# MainSheet.net
KiCad netlist of a schematic drawn in Altium Designer
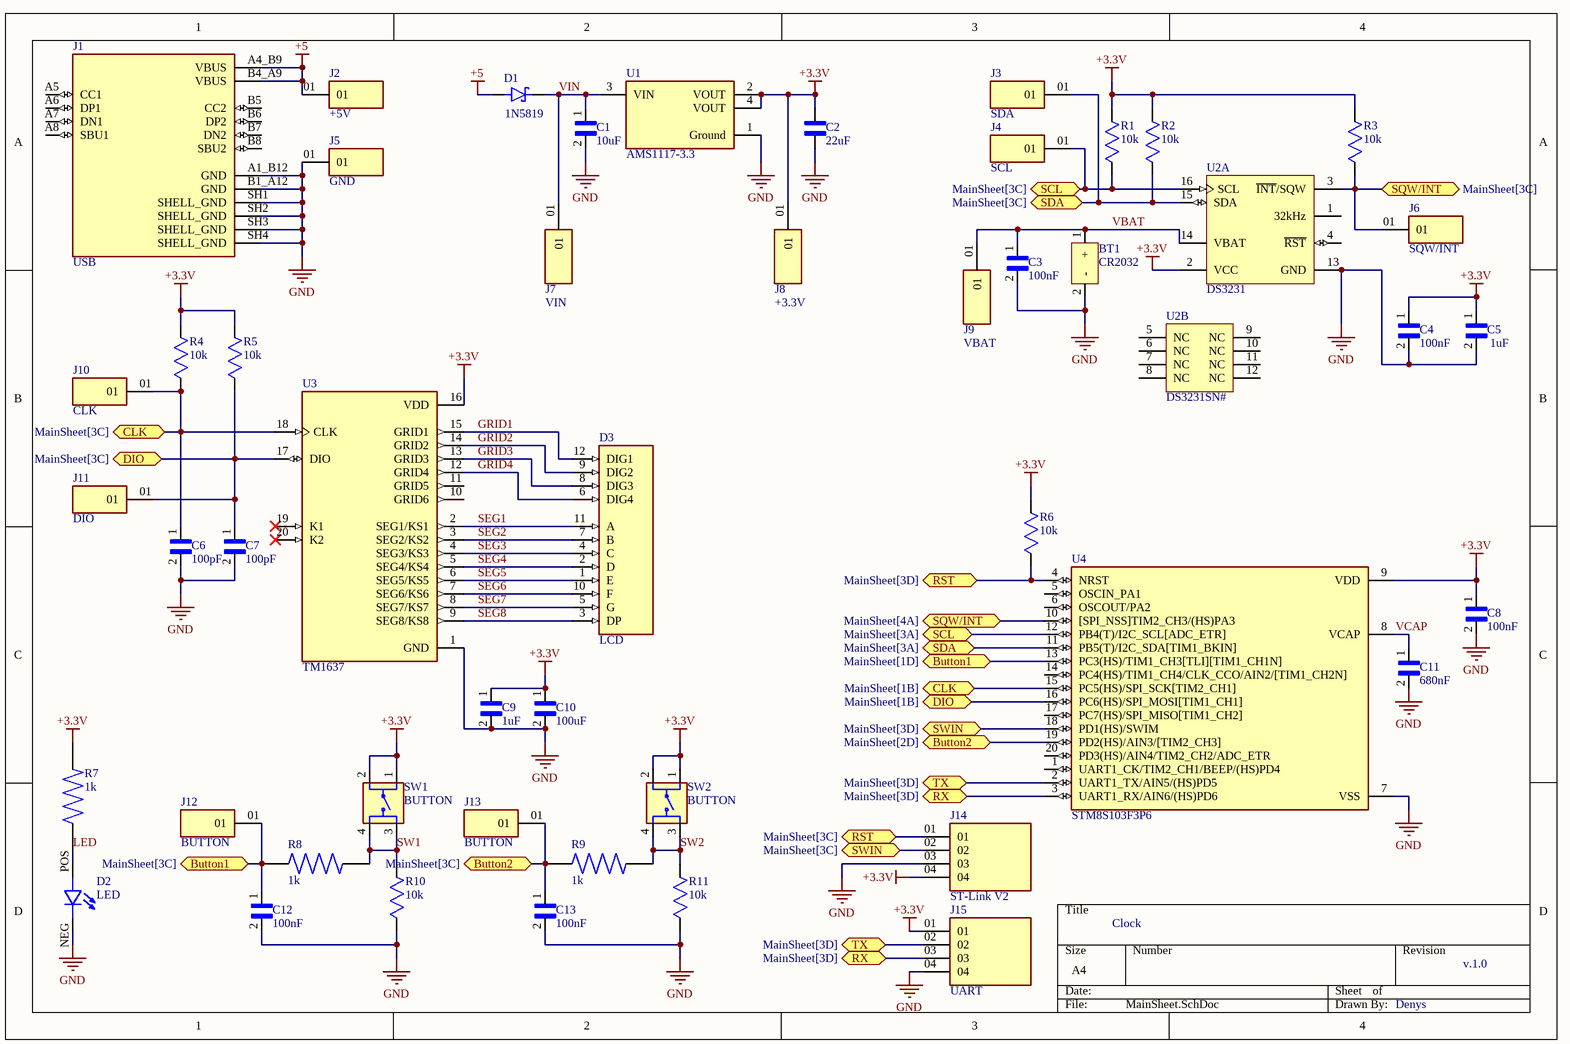
[diagram p0: MainSheet.SchDoc]

(export (version "E")
  (design (tool "Eeschema 10.0.6"))
  (components
    (comp (ref "BT1")
      (value "CR2032")
      (footprint "PCB_Battery")
      (description "Cell Holder for CR2032")
      (libsource (lib "CR2032") (part "Battery"))
    )
    (comp (ref "C1")
      (value "10uF")
      (footprint "CAPC3216X190")
      (description "Cap Ceramic 10uF 25V B 10% Pad SMD 1206 85Â°C T/R")
      (fields (field (name "MP") "GRM31CB31E106KA75L"))
      (libsource (lib "GRM31CB31E106KA75L_new") (part "GRM31CB31E106KA75L"))
    )
    (comp (ref "C2")
      (value "22uF")
      (footprint "CAPC3216X125N")
      (fields (field (name "MP") "altium_native_batch"))
      (libsource (lib "GRM31CR61E226KE15L") (part "GRM31CR61E226KE15L"))
    )
    (comp (ref "C3")
      (value "100nF")
      (footprint "CAPC3216X180N")
      (description "Ceramic capacitor SMD 1206 100 nF 50 V 10 % Samsung Electro-Mechanics CL31B104KBCNNNC 4000 pc(s)")
      (fields (field (name "MP") "CL31B104KBCNNNC") (field (name "MF") "Samsung Electro-Mechanics"))
      (libsource (lib "CL31B104KBCNNNC") (part "CL31B104KBCNNNC"))
    )
    (comp (ref "C4")
      (value "100nF")
      (footprint "CAPC3216X180N")
      (description "Ceramic capacitor SMD 1206 100 nF 50 V 10 % Samsung Electro-Mechanics CL31B104KBCNNNC 4000 pc(s)")
      (fields (field (name "MP") "CL31B104KBCNNNC") (field (name "MF") "Samsung Electro-Mechanics"))
      (libsource (lib "CL31B104KBCNNNC") (part "CL31B104KBCNNNC"))
    )
    (comp (ref "C5")
      (value "1uF")
      (footprint "CAPC3216X110N")
      (description "CAP CER 1UF 25V X7R 1206")
      (fields (field (name "MP") "C1206C105J3RACTU"))
      (libsource (lib "C_1206_1uF") (part "C1206C105J3RACTU"))
    )
    (comp (ref "C6")
      (value "100pF")
      (footprint "CAPC3216X110N")
      (description "CAP, MLCC, C0G, 100PF, 630V, 1206")
      (fields (field (name "MP") "C1206C101JBGACTU"))
      (libsource (lib "C_1206_100pF") (part "C1206C101JBGACTU"))
    )
    (comp (ref "C7")
      (value "100pF")
      (footprint "CAPC3216X110N")
      (description "CAP, MLCC, C0G, 100PF, 630V, 1206")
      (fields (field (name "MP") "C1206C101JBGACTU"))
      (libsource (lib "C_1206_100pF") (part "C1206C101JBGACTU"))
    )
    (comp (ref "C8")
      (value "100nF")
      (footprint "CAPC3216X180N")
      (description "Ceramic capacitor SMD 1206 100 nF 50 V 10 % Samsung Electro-Mechanics CL31B104KBCNNNC 4000 pc(s)")
      (fields (field (name "MP") "CL31B104KBCNNNC") (field (name "MF") "Samsung Electro-Mechanics"))
      (libsource (lib "CL31B104KBCNNNC") (part "CL31B104KBCNNNC"))
    )
    (comp (ref "C9")
      (value "1uF")
      (footprint "CAPC3216X110N")
      (description "CAP CER 1UF 25V X7R 1206")
      (fields (field (name "MP") "C1206C105J3RACTU"))
      (libsource (lib "C_1206_1uF") (part "C1206C105J3RACTU"))
    )
    (comp (ref "C10")
      (value "100uF")
      (footprint "CAP3216X125N")
      (description "100礔 卤10% 6.3V Ceramic Capacitor X5R 1206 _3216 Metric_")
      (fields (field (name "MF") "Murata Electronics") (field (name "MP") "GRM31CR60J107KE39L"))
      (libsource (lib "C_1206_100uF") (part "GRM31CR60J107KE39L"))
    )
    (comp (ref "C11")
      (value "680nF")
      (footprint "CAPC3216X110N")
      (description ".68UF 50V 10% 1206")
      (fields (field (name "MP") "C1206C684K5RACTU"))
      (libsource (lib "C_1206_680nF") (part "C1206C684K5RACTU"))
    )
    (comp (ref "C12")
      (value "100nF")
      (footprint "CAPC3216X180N")
      (description "Ceramic capacitor SMD 1206 100 nF 50 V 10 % Samsung Electro-Mechanics CL31B104KBCNNNC 4000 pc(s)")
      (fields (field (name "MP") "CL31B104KBCNNNC") (field (name "MF") "Samsung Electro-Mechanics"))
      (libsource (lib "CL31B104KBCNNNC") (part "CL31B104KBCNNNC"))
    )
    (comp (ref "C13")
      (value "100nF")
      (footprint "CAPC3216X180N")
      (description "Ceramic capacitor SMD 1206 100 nF 50 V 10 % Samsung Electro-Mechanics CL31B104KBCNNNC 4000 pc(s)")
      (fields (field (name "MP") "CL31B104KBCNNNC") (field (name "MF") "Samsung Electro-Mechanics"))
      (libsource (lib "CL31B104KBCNNNC") (part "CL31B104KBCNNNC"))
    )
    (comp (ref "D1")
      (value "1N5819")
      (footprint "SOD3715X145N")
      (description "Diode Schottky 40 V 1A Surface Mount SOD-123")
      (fields (field (name "MF") "Diodes Inc.") (field (name "MP") "1N5819HW-7"))
      (libsource (lib "1N5819HW-7") (part "1N5819HW-7"))
    )
    (comp (ref "D2")
      (value "LED")
      (footprint "LED_1206:LEDC3216X120N")
      (description "2.6 V Red LED SMD")
      (fields (field (name "MP") "LHN974 RED LED 1206") (field (name "MF") "Osram"))
      (libsource (lib "LED_1206") (part "LHN974_RED_LED_1206"))
    )
    (comp (ref "D3")
      (value "LCD")
      (footprint "LED_LDQ-M3604RI")
      (description "Display, Seven Segment, 9.2MM, Red")
      (fields (field (name "MF") "Lumex") (field (name "MP") "LDQ-M3604RI"))
      (libsource (lib "LED_clock") (part "LDQ-M3604RI"))
    )
    (comp (ref "J1")
      (value "USB")
      (footprint "GCT_USB4105-GF-A")
      (fields (field (name "MF") "{'manufacturer': u'GCT'}") (field (name "MP") "USB4105-GF-A"))
      (libsource (lib "USB4105-GF-A_new") (part "USB4105-GF-A"))
    )
    (comp (ref "J2")
      (value "+5V")
      (footprint "SAMTEC_MTMM-101-X-X-S-X")
      (description "Connector Header Through Hole 1 position")
      (fields (field (name "MF") "Samtec") (field (name "MP") "MTMM-101-05-G-S-225"))
      (libsource (lib "") (part "MTMM-101-X-X-S-X_2"))
    )
    (comp (ref "J3")
      (value "SDA")
      (footprint "SAMTEC_MTMM-101-X-X-S-X")
      (description "Connector Header Through Hole 1 position")
      (fields (field (name "MF") "Samtec") (field (name "MP") "MTMM-101-05-G-S-225"))
      (libsource (lib "") (part "MTMM-101-X-X-S-X_1"))
    )
    (comp (ref "J4")
      (value "SCL")
      (footprint "SAMTEC_MTMM-101-X-X-S-X")
      (description "Connector Header Through Hole 1 position")
      (fields (field (name "MF") "Samtec") (field (name "MP") "MTMM-101-05-G-S-225"))
      (libsource (lib "") (part "MTMM-101-X-X-S-X_1"))
    )
    (comp (ref "J5")
      (value "GND")
      (footprint "SAMTEC_MTMM-101-X-X-S-X")
      (description "Connector Header Through Hole 1 position")
      (fields (field (name "MF") "Samtec") (field (name "MP") "MTMM-101-05-G-S-225"))
      (libsource (lib "") (part "MTMM-101-X-X-S-X_2"))
    )
    (comp (ref "J6")
      (value "SQW/INT")
      (footprint "SAMTEC_MTMM-101-X-X-S-X")
      (description "Connector Header Through Hole 1 position")
      (fields (field (name "MF") "Samtec") (field (name "MP") "MTMM-101-05-G-S-225"))
      (libsource (lib "") (part "MTMM-101-X-X-S-X_2"))
    )
    (comp (ref "J7")
      (value "VIN")
      (footprint "SAMTEC_MTMM-101-X-X-S-X")
      (description "Connector Header Through Hole 1 position")
      (fields (field (name "MF") "Samtec") (field (name "MP") "MTMM-101-05-G-S-225"))
      (libsource (lib "MTMM-101-X-X-S-X") (part "MTMM-101-X-X-S-X"))
    )
    (comp (ref "J8")
      (value "+3.3V")
      (footprint "SAMTEC_MTMM-101-X-X-S-X")
      (description "Connector Header Through Hole 1 position")
      (fields (field (name "MF") "Samtec") (field (name "MP") "MTMM-101-05-G-S-225"))
      (libsource (lib "MTMM-101-X-X-S-X") (part "MTMM-101-X-X-S-X"))
    )
    (comp (ref "J9")
      (value "VBAT")
      (footprint "SAMTEC_MTMM-101-X-X-S-X")
      (description "Connector Header Through Hole 1 position")
      (fields (field (name "MF") "Samtec") (field (name "MP") "MTMM-101-05-G-S-225"))
      (libsource (lib "MTMM-101-X-X-S-X") (part "MTMM-101-X-X-S-X"))
    )
    (comp (ref "J10")
      (value "CLK")
      (footprint "SAMTEC_MTMM-101-X-X-S-X")
      (description "Connector Header Through Hole 1 position")
      (fields (field (name "MF") "Samtec") (field (name "MP") "MTMM-101-05-G-S-225"))
      (libsource (lib "") (part "MTMM-101-X-X-S-X_1"))
    )
    (comp (ref "J11")
      (value "DIO")
      (footprint "SAMTEC_MTMM-101-X-X-S-X")
      (description "Connector Header Through Hole 1 position")
      (fields (field (name "MF") "Samtec") (field (name "MP") "MTMM-101-05-G-S-225"))
      (libsource (lib "") (part "MTMM-101-X-X-S-X_1"))
    )
    (comp (ref "J12")
      (value "BUTTON")
      (footprint "SAMTEC_MTMM-101-X-X-S-X")
      (description "Connector Header Through Hole 1 position")
      (fields (field (name "MF") "Samtec") (field (name "MP") "MTMM-101-05-G-S-225"))
      (libsource (lib "") (part "MTMM-101-X-X-S-X_1"))
    )
    (comp (ref "J13")
      (value "BUTTON")
      (footprint "SAMTEC_MTMM-101-X-X-S-X")
      (description "Connector Header Through Hole 1 position")
      (fields (field (name "MF") "Samtec") (field (name "MP") "MTMM-101-05-G-S-225"))
      (libsource (lib "") (part "MTMM-101-X-X-S-X_1"))
    )
    (comp (ref "J14")
      (value "ST-Link V2")
      (footprint "SAMTEC_TSW-104-07-S-S")
      (fields (field (name "MF") "Samtec Inc.") (field (name "MP") "TSW-104-07-S-S"))
      (libsource (lib "TSW-104-07-S-S") (part "TSW-104-07-S-S"))
    )
    (comp (ref "J15")
      (value "UART")
      (footprint "SAMTEC_TSW-104-07-S-S")
      (fields (field (name "MF") "Samtec Inc.") (field (name "MP") "TSW-104-07-S-S"))
      (libsource (lib "TSW-104-07-S-S") (part "TSW-104-07-S-S"))
    )
    (comp (ref "R1")
      (value "10k")
      (footprint "RESC3216X71N")
      (fields (field (name "MF") "Yageo Corporation") (field (name "MP") "RC1206FR0710KL"))
      (libsource (lib "RC1206FR-0710KL") (part "RC1206FR-0710KL"))
    )
    (comp (ref "R2")
      (value "10k")
      (footprint "RESC3216X71N")
      (fields (field (name "MF") "Yageo Corporation") (field (name "MP") "RC1206FR0710KL"))
      (libsource (lib "RC1206FR-0710KL") (part "RC1206FR-0710KL"))
    )
    (comp (ref "R3")
      (value "10k")
      (footprint "RESC3216X71N")
      (fields (field (name "MF") "Yageo Corporation") (field (name "MP") "RC1206FR0710KL"))
      (libsource (lib "RC1206FR-0710KL") (part "RC1206FR-0710KL"))
    )
    (comp (ref "R4")
      (value "10k")
      (footprint "RESC3216X71N")
      (fields (field (name "MF") "Yageo Corporation") (field (name "MP") "RC1206FR0710KL"))
      (libsource (lib "RC1206FR-0710KL") (part "RC1206FR-0710KL"))
    )
    (comp (ref "R5")
      (value "10k")
      (footprint "RESC3216X71N")
      (fields (field (name "MF") "Yageo Corporation") (field (name "MP") "RC1206FR0710KL"))
      (libsource (lib "RC1206FR-0710KL") (part "RC1206FR-0710KL"))
    )
    (comp (ref "R6")
      (value "10k")
      (footprint "RESC3216X71N")
      (fields (field (name "MF") "Yageo Corporation") (field (name "MP") "RC1206FR0710KL"))
      (libsource (lib "RC1206FR-0710KL") (part "RC1206FR-0710KL"))
    )
    (comp (ref "R7")
      (value "1k")
      (footprint "RESC3116X65N")
      (description "Surge Chip Resistor Automotive Grade Thick Film 1206 1kOhm 1% Paper T/R")
      (fields (field (name "MF") "Yageo Corporation") (field (name "MP") "SR1206FR071KL"))
      (libsource (lib "SR1206FR-071KL") (part "SR1206FR-071KL"))
    )
    (comp (ref "R8")
      (value "1k")
      (footprint "RESC3116X65N")
      (description "Surge Chip Resistor Automotive Grade Thick Film 1206 1kOhm 1% Paper T/R")
      (fields (field (name "MF") "Yageo Corporation") (field (name "MP") "SR1206FR071KL"))
      (libsource (lib "SR1206FR-071KL") (part "SR1206FR-071KL"))
    )
    (comp (ref "R9")
      (value "1k")
      (footprint "RESC3116X65N")
      (description "Surge Chip Resistor Automotive Grade Thick Film 1206 1kOhm 1% Paper T/R")
      (fields (field (name "MF") "Yageo Corporation") (field (name "MP") "SR1206FR071KL"))
      (libsource (lib "SR1206FR-071KL") (part "SR1206FR-071KL"))
    )
    (comp (ref "R10")
      (value "10k")
      (footprint "RESC3216X71N")
      (fields (field (name "MF") "Yageo Corporation") (field (name "MP") "RC1206FR0710KL"))
      (libsource (lib "RC1206FR-0710KL") (part "RC1206FR-0710KL"))
    )
    (comp (ref "R11")
      (value "10k")
      (footprint "RESC3216X71N")
      (fields (field (name "MF") "Yageo Corporation") (field (name "MP") "RC1206FR0710KL"))
      (libsource (lib "RC1206FR-0710KL") (part "RC1206FR-0710KL"))
    )
    (comp (ref "SW1")
      (value "BUTTON")
      (footprint "TE_4-1437565-9")
      (description "Alcoswitch, Switch, Tactile, 50 mA, SPST, Pushbutton, Off[On], FSM6JSMA ¦ TE Connectivity FSM6JSMA")
      (fields (field (name "MF") "TE Connectivity") (field (name "MP") "FSM6JSMA"))
      (libsource (lib "4-1437565-9") (part "4-1437565-9"))
    )
    (comp (ref "SW2")
      (value "BUTTON")
      (footprint "TE_4-1437565-9")
      (description "Alcoswitch, Switch, Tactile, 50 mA, SPST, Pushbutton, Off[On], FSM6JSMA ¦ TE Connectivity FSM6JSMA")
      (fields (field (name "MF") "TE Connectivity") (field (name "MP") "FSM6JSMA"))
      (libsource (lib "4-1437565-9") (part "4-1437565-9"))
    )
    (comp (ref "U1")
      (value "AMS1117-3.3")
      (footprint "FP-AMS1117-IPC_A")
      (description "LDO Voltage Regulators 1A, 3.3V")
      (fields
        (field (name "OCTOPART") "https://octopart.com/ams1117-3.3-advanced+monolithic+systems-25899300")
        (field (name "MANUFACTURER") "Advanced Monolithic Systems")
      )
      (libsource (lib "Altium Content Vault") (part "8bdbb5f8e77002000e30dd2845d0354"))
    )
    (comp (ref "U2")
      (value "DS3231")
      (footprint "W16#H2_N")
      (libsource (lib "Altium Content Vault") (part "MAX-RTC-16-DS3231S-W16#H2"))
    )
    (comp (ref "U3")
      (value "TM1637")
      (footprint "SOIC127P1035X255-20N")
      (description "LED Drive Control Special Circuit")
      (fields (field (name "MF") "Titan Micro Electronics") (field (name "MP") "TM1637_SOP20"))
      (libsource (lib "TM1637_SOP20") (part "TM1637_SOP20"))
    )
    (comp (ref "U4")
      (value "STM8S103F3P6")
      (footprint "SOP65P640X120-20N")
      (description "STM8 series Microcontroller IC 8-Bit 16MHz 8KB (8K x 8) FLASH 20-TSSOP")
      (fields (field (name "MF") "STMicroelectronics"))
      (libsource (lib "STM8S103F3P6_new") (part "STM8S103F3P6"))
    )
  )
  (nets
    (net (code "1") (name "+3.3V") (class "Default")
      (node (ref "C10") (pin "1") (pinfunction "1_1") (pintype "passive"))
      (node (ref "C2") (pin "2") (pinfunction "2_2") (pintype "passive"))
      (node (ref "C4") (pin "1") (pinfunction "1_1") (pintype "passive"))
      (node (ref "C5") (pin "1") (pinfunction "1_1") (pintype "passive"))
      (node (ref "C8") (pin "1") (pinfunction "1_1") (pintype "passive"))
      (node (ref "C9") (pin "1") (pinfunction "1_1") (pintype "passive"))
      (node (ref "J14") (pin "04") (pinfunction "04_04") (pintype "passive"))
      (node (ref "J15") (pin "01") (pinfunction "01_01") (pintype "passive"))
      (node (ref "J8") (pin "01") (pinfunction "01_01") (pintype "passive"))
      (node (ref "R1") (pin "1") (pinfunction "R1_1") (pintype "passive"))
      (node (ref "R2") (pin "1") (pinfunction "R1_1") (pintype "passive"))
      (node (ref "R3") (pin "1") (pinfunction "R1_1") (pintype "passive"))
      (node (ref "R4") (pin "1") (pinfunction "R1_1") (pintype "passive"))
      (node (ref "R5") (pin "1") (pinfunction "R1_1") (pintype "passive"))
      (node (ref "R6") (pin "1") (pinfunction "R1_1") (pintype "passive"))
      (node (ref "R7") (pin "2") (pinfunction "2_2") (pintype "passive"))
      (node (ref "SW1") (pin "1") (pinfunction "1_1") (pintype "passive"))
      (node (ref "SW1") (pin "2") (pinfunction "2_2") (pintype "passive"))
      (node (ref "SW2") (pin "1") (pinfunction "1_1") (pintype "passive"))
      (node (ref "SW2") (pin "2") (pinfunction "2_2") (pintype "passive"))
      (node (ref "U1") (pin "2") (pinfunction "VOUT_2") (pintype "passive"))
      (node (ref "U1") (pin "4") (pinfunction "VOUT_4") (pintype "passive"))
      (node (ref "U2") (pin "2") (pinfunction "VCC_2") (pintype "power_in"))
      (node (ref "U3") (pin "16") (pinfunction "VDD_16") (pintype "power_in"))
      (node (ref "U4") (pin "9") (pinfunction "VDD_9") (pintype "power_in"))
    )
    (net (code "2") (name "+5") (class "Default")
      (node (ref "D1") (pin "A") (pinfunction "A_A") (pintype "passive"))
      (node (ref "J1") (pin "A4_B9") (pinfunction "VBUS_A4_B9") (pintype "power_in"))
      (node (ref "J1") (pin "B4_A9") (pinfunction "VBUS_B4_A9") (pintype "power_in"))
      (node (ref "J2") (pin "01") (pinfunction "01_01") (pintype "passive"))
    )
    (net (code "3") (name "/Button1") (class "Default")
      (node (ref "C12") (pin "1") (pinfunction "1_1") (pintype "passive"))
      (node (ref "J12") (pin "01") (pinfunction "01_01") (pintype "passive"))
      (node (ref "R8") (pin "2") (pinfunction "2_2") (pintype "passive"))
      (node (ref "U4") (pin "13") (pinfunction "PC3(HS)/TIM1_CH3[TLI][TIM1_CH1N]_13") (pintype "bidirectional"))
    )
    (net (code "4") (name "/Button2") (class "Default")
      (node (ref "C13") (pin "1") (pinfunction "1_1") (pintype "passive"))
      (node (ref "J13") (pin "01") (pinfunction "01_01") (pintype "passive"))
      (node (ref "R9") (pin "2") (pinfunction "2_2") (pintype "passive"))
      (node (ref "U4") (pin "19") (pinfunction "PD2(HS)/AIN3/[TIM2_CH3]_19") (pintype "bidirectional"))
    )
    (net (code "5") (name "/CLK") (class "Default")
      (node (ref "C6") (pin "1") (pinfunction "1_1") (pintype "passive"))
      (node (ref "J10") (pin "01") (pinfunction "01_01") (pintype "passive"))
      (node (ref "R4") (pin "2") (pinfunction "R2_2") (pintype "passive"))
      (node (ref "U3") (pin "18") (pinfunction "CLK_18") (pintype "input"))
      (node (ref "U4") (pin "15") (pinfunction "PC5(HS)/SPI_SCK[TIM2_CH1]_15") (pintype "bidirectional"))
    )
    (net (code "6") (name "/DIO") (class "Default")
      (node (ref "C7") (pin "1") (pinfunction "1_1") (pintype "passive"))
      (node (ref "J11") (pin "01") (pinfunction "01_01") (pintype "passive"))
      (node (ref "R5") (pin "2") (pinfunction "R2_2") (pintype "passive"))
      (node (ref "U3") (pin "17") (pinfunction "DIO_17") (pintype "bidirectional"))
      (node (ref "U4") (pin "16") (pinfunction "PC6(HS)/SPI_MOSI[TIM1_CH1]_16") (pintype "bidirectional"))
    )
    (net (code "7") (name "/GRID1") (class "Default")
      (node (ref "D3") (pin "12") (pinfunction "DIG1_12") (pintype "input"))
      (node (ref "U3") (pin "15") (pinfunction "GRID1_15") (pintype "output"))
    )
    (net (code "8") (name "/GRID2") (class "Default")
      (node (ref "D3") (pin "9") (pinfunction "DIG2_9") (pintype "input"))
      (node (ref "U3") (pin "14") (pinfunction "GRID2_14") (pintype "output"))
    )
    (net (code "9") (name "/GRID3") (class "Default")
      (node (ref "D3") (pin "8") (pinfunction "DIG3_8") (pintype "input"))
      (node (ref "U3") (pin "13") (pinfunction "GRID3_13") (pintype "output"))
    )
    (net (code "10") (name "/GRID4") (class "Default")
      (node (ref "D3") (pin "6") (pinfunction "DIG4_6") (pintype "input"))
      (node (ref "U3") (pin "12") (pinfunction "GRID4_12") (pintype "output"))
    )
    (net (code "11") (name "/LED") (class "Default")
      (node (ref "D2") (pin "POS") (pinfunction "POS_POS") (pintype "passive"))
      (node (ref "R7") (pin "1") (pinfunction "1_1") (pintype "passive"))
    )
    (net (code "12") (name "/RST") (class "Default")
      (node (ref "J14") (pin "01") (pinfunction "01_01") (pintype "passive"))
      (node (ref "R6") (pin "2") (pinfunction "R2_2") (pintype "passive"))
      (node (ref "U4") (pin "4") (pinfunction "NRST_4") (pintype "bidirectional"))
    )
    (net (code "13") (name "/RX") (class "Default")
      (node (ref "J15") (pin "03") (pinfunction "03_03") (pintype "passive"))
      (node (ref "U4") (pin "3") (pinfunction "UART1_RX/AIN6/(HS)PD6_3") (pintype "bidirectional"))
    )
    (net (code "14") (name "/SCL") (class "Default")
      (node (ref "J4") (pin "01") (pinfunction "01_01") (pintype "passive"))
      (node (ref "R1") (pin "2") (pinfunction "R2_2") (pintype "passive"))
      (node (ref "U2") (pin "16") (pinfunction "SCL_16") (pintype "input"))
      (node (ref "U4") (pin "12") (pinfunction "PB4(T)/I2C_SCL[ADC_ETR]_12") (pintype "bidirectional"))
    )
    (net (code "15") (name "/SDA") (class "Default")
      (node (ref "J3") (pin "01") (pinfunction "01_01") (pintype "passive"))
      (node (ref "R2") (pin "2") (pinfunction "R2_2") (pintype "passive"))
      (node (ref "U2") (pin "15") (pinfunction "SDA_15") (pintype "bidirectional"))
      (node (ref "U4") (pin "11") (pinfunction "PB5(T)/I2C_SDA[TIM1_BKIN]_11") (pintype "bidirectional"))
    )
    (net (code "16") (name "/SEG1") (class "Default")
      (node (ref "D3") (pin "11") (pinfunction "A_11") (pintype "input"))
      (node (ref "U3") (pin "2") (pinfunction "SEG1/KS1_2") (pintype "output"))
    )
    (net (code "17") (name "/SEG2") (class "Default")
      (node (ref "D3") (pin "7") (pinfunction "B_7") (pintype "input"))
      (node (ref "U3") (pin "3") (pinfunction "SEG2/KS2_3") (pintype "output"))
    )
    (net (code "18") (name "/SEG3") (class "Default")
      (node (ref "D3") (pin "4") (pinfunction "C_4") (pintype "input"))
      (node (ref "U3") (pin "4") (pinfunction "SEG3/KS3_4") (pintype "output"))
    )
    (net (code "19") (name "/SEG4") (class "Default")
      (node (ref "D3") (pin "2") (pinfunction "D_2") (pintype "input"))
      (node (ref "U3") (pin "5") (pinfunction "SEG4/KS4_5") (pintype "output"))
    )
    (net (code "20") (name "/SEG5") (class "Default")
      (node (ref "D3") (pin "1") (pinfunction "E_1") (pintype "input"))
      (node (ref "U3") (pin "6") (pinfunction "SEG5/KS5_6") (pintype "output"))
    )
    (net (code "21") (name "/SEG6") (class "Default")
      (node (ref "D3") (pin "10") (pinfunction "F_10") (pintype "input"))
      (node (ref "U3") (pin "7") (pinfunction "SEG6/KS6_7") (pintype "output"))
    )
    (net (code "22") (name "/SEG7") (class "Default")
      (node (ref "D3") (pin "5") (pinfunction "G_5") (pintype "input"))
      (node (ref "U3") (pin "8") (pinfunction "SEG7/KS7_8") (pintype "output"))
    )
    (net (code "23") (name "/SEG8") (class "Default")
      (node (ref "D3") (pin "3") (pinfunction "DP_3") (pintype "input"))
      (node (ref "U3") (pin "9") (pinfunction "SEG8/KS8_9") (pintype "output"))
    )
    (net (code "24") (name "/SQW{slash}INT") (class "Default")
      (node (ref "J6") (pin "01") (pinfunction "01_01") (pintype "passive"))
      (node (ref "R3") (pin "2") (pinfunction "R2_2") (pintype "passive"))
      (node (ref "U2") (pin "3") (pinfunction "~{INT}/SQW_3") (pintype "open_collector"))
      (node (ref "U4") (pin "10") (pinfunction "[SPI_NSS]TIM2_CH3/(HS)PA3_10") (pintype "bidirectional"))
    )
    (net (code "25") (name "/SW1") (class "Default")
      (node (ref "R10") (pin "1") (pinfunction "R1_1") (pintype "passive"))
      (node (ref "R8") (pin "1") (pinfunction "1_1") (pintype "passive"))
      (node (ref "SW1") (pin "3") (pinfunction "3_3") (pintype "passive"))
      (node (ref "SW1") (pin "4") (pinfunction "4_4") (pintype "passive"))
    )
    (net (code "26") (name "/SW2") (class "Default")
      (node (ref "R11") (pin "1") (pinfunction "R1_1") (pintype "passive"))
      (node (ref "R9") (pin "1") (pinfunction "1_1") (pintype "passive"))
      (node (ref "SW2") (pin "3") (pinfunction "3_3") (pintype "passive"))
      (node (ref "SW2") (pin "4") (pinfunction "4_4") (pintype "passive"))
    )
    (net (code "27") (name "/SWIN") (class "Default")
      (node (ref "J14") (pin "02") (pinfunction "02_02") (pintype "passive"))
      (node (ref "U4") (pin "18") (pinfunction "PD1(HS)/SWIM_18") (pintype "bidirectional"))
    )
    (net (code "28") (name "/TX") (class "Default")
      (node (ref "J15") (pin "02") (pinfunction "02_02") (pintype "passive"))
      (node (ref "U4") (pin "2") (pinfunction "UART1_TX/AIN5/(HS)PD5_2") (pintype "bidirectional"))
    )
    (net (code "29") (name "/VBAT") (class "Default")
      (node (ref "BT1") (pin "1") (pinfunction "+_1") (pintype "power_in"))
      (node (ref "C3") (pin "1") (pinfunction "1_1") (pintype "passive"))
      (node (ref "J9") (pin "01") (pinfunction "01_01") (pintype "passive"))
      (node (ref "U2") (pin "14") (pinfunction "VBAT_14") (pintype "power_in"))
    )
    (net (code "30") (name "/VCAP") (class "Default")
      (node (ref "C11") (pin "1") (pinfunction "1_1") (pintype "passive"))
      (node (ref "U4") (pin "8") (pinfunction "VCAP_8") (pintype "passive"))
    )
    (net (code "31") (name "/VIN") (class "Default")
      (node (ref "C1") (pin "1") (pinfunction "1_1") (pintype "passive"))
      (node (ref "D1") (pin "C") (pinfunction "K_C") (pintype "passive"))
      (node (ref "J7") (pin "01") (pinfunction "01_01") (pintype "passive"))
      (node (ref "U1") (pin "3") (pinfunction "VIN_3") (pintype "power_in"))
    )
    (net (code "32") (name "GND") (class "Default")
      (node (ref "BT1") (pin "2") (pinfunction "-_2") (pintype "power_in"))
      (node (ref "C1") (pin "2") (pinfunction "2_2") (pintype "passive"))
      (node (ref "C10") (pin "2") (pinfunction "2_2") (pintype "passive"))
      (node (ref "C11") (pin "2") (pinfunction "2_2") (pintype "passive"))
      (node (ref "C12") (pin "2") (pinfunction "2_2") (pintype "passive"))
      (node (ref "C13") (pin "2") (pinfunction "2_2") (pintype "passive"))
      (node (ref "C2") (pin "1") (pinfunction "1_1") (pintype "passive"))
      (node (ref "C3") (pin "2") (pinfunction "2_2") (pintype "passive"))
      (node (ref "C4") (pin "2") (pinfunction "2_2") (pintype "passive"))
      (node (ref "C5") (pin "2") (pinfunction "2_2") (pintype "passive"))
      (node (ref "C6") (pin "2") (pinfunction "2_2") (pintype "passive"))
      (node (ref "C7") (pin "2") (pinfunction "2_2") (pintype "passive"))
      (node (ref "C8") (pin "2") (pinfunction "2_2") (pintype "passive"))
      (node (ref "C9") (pin "2") (pinfunction "2_2") (pintype "passive"))
      (node (ref "D2") (pin "NEG") (pinfunction "NEG_NEG") (pintype "passive"))
      (node (ref "J1") (pin "A1_B12") (pinfunction "GND_A1_B12") (pintype "power_in"))
      (node (ref "J1") (pin "B1_A12") (pinfunction "GND_B1_A12") (pintype "power_in"))
      (node (ref "J1") (pin "SH1") (pinfunction "SHELL_GND_SH1") (pintype "power_in"))
      (node (ref "J1") (pin "SH2") (pinfunction "SHELL_GND_SH2") (pintype "power_in"))
      (node (ref "J1") (pin "SH3") (pinfunction "SHELL_GND_SH3") (pintype "power_in"))
      (node (ref "J1") (pin "SH4") (pinfunction "SHELL_GND_SH4") (pintype "power_in"))
      (node (ref "J14") (pin "03") (pinfunction "03_03") (pintype "passive"))
      (node (ref "J15") (pin "04") (pinfunction "04_04") (pintype "passive"))
      (node (ref "J5") (pin "01") (pinfunction "01_01") (pintype "passive"))
      (node (ref "R10") (pin "2") (pinfunction "R2_2") (pintype "passive"))
      (node (ref "R11") (pin "2") (pinfunction "R2_2") (pintype "passive"))
      (node (ref "U1") (pin "1") (pinfunction "Ground_1") (pintype "power_in"))
      (node (ref "U2") (pin "13") (pinfunction "GND_13") (pintype "power_in"))
      (node (ref "U3") (pin "1") (pinfunction "GND_1") (pintype "power_in"))
      (node (ref "U4") (pin "7") (pinfunction "VSS_7") (pintype "power_in"))
    )
    (net (code "33") (name "unconnected-(J1-CC1-PadA5)") (class "Default")
      (node (ref "J1") (pin "A5") (pinfunction "CC1_A5") (pintype "bidirectional"))
    )
    (net (code "34") (name "unconnected-(J1-CC2-PadB5)") (class "Default")
      (node (ref "J1") (pin "B5") (pinfunction "CC2_B5") (pintype "bidirectional"))
    )
    (net (code "35") (name "unconnected-(J1-DN1-PadA7)") (class "Default")
      (node (ref "J1") (pin "A7") (pinfunction "DN1_A7") (pintype "bidirectional"))
    )
    (net (code "36") (name "unconnected-(J1-DN2-PadB7)") (class "Default")
      (node (ref "J1") (pin "B7") (pinfunction "DN2_B7") (pintype "bidirectional"))
    )
    (net (code "37") (name "unconnected-(J1-DP1-PadA6)") (class "Default")
      (node (ref "J1") (pin "A6") (pinfunction "DP1_A6") (pintype "bidirectional"))
    )
    (net (code "38") (name "unconnected-(J1-DP2-PadB6)") (class "Default")
      (node (ref "J1") (pin "B6") (pinfunction "DP2_B6") (pintype "bidirectional"))
    )
    (net (code "39") (name "unconnected-(J1-SBU1-PadA8)") (class "Default")
      (node (ref "J1") (pin "A8") (pinfunction "SBU1_A8") (pintype "bidirectional"))
    )
    (net (code "40") (name "unconnected-(J1-SBU2-PadB8)") (class "Default")
      (node (ref "J1") (pin "B8") (pinfunction "SBU2_B8") (pintype "bidirectional"))
    )
    (net (code "41") (name "unconnected-(U2A-32kHz-Pad1)") (class "Default")
      (node (ref "U2") (pin "1") (pinfunction "32kHz_1") (pintype "open_collector"))
    )
    (net (code "42") (name "unconnected-(U2A-~{RST}-Pad4)") (class "Default")
      (node (ref "U2") (pin "4") (pinfunction "~{RST}_4") (pintype "bidirectional"))
    )
    (net (code "43") (name "unconnected-(U2B-NC-Pad5)") (class "Default")
      (node (ref "U2") (pin "5") (pinfunction "NC_5") (pintype "passive"))
    )
    (net (code "44") (name "unconnected-(U2B-NC-Pad6)") (class "Default")
      (node (ref "U2") (pin "6") (pinfunction "NC_6") (pintype "passive"))
    )
    (net (code "45") (name "unconnected-(U2B-NC-Pad7)") (class "Default")
      (node (ref "U2") (pin "7") (pinfunction "NC_7") (pintype "passive"))
    )
    (net (code "46") (name "unconnected-(U2B-NC-Pad8)") (class "Default")
      (node (ref "U2") (pin "8") (pinfunction "NC_8") (pintype "passive"))
    )
    (net (code "47") (name "unconnected-(U2B-NC-Pad9)") (class "Default")
      (node (ref "U2") (pin "9") (pinfunction "NC_9") (pintype "passive"))
    )
    (net (code "48") (name "unconnected-(U2B-NC-Pad10)") (class "Default")
      (node (ref "U2") (pin "10") (pinfunction "NC_10") (pintype "passive"))
    )
    (net (code "49") (name "unconnected-(U2B-NC-Pad11)") (class "Default")
      (node (ref "U2") (pin "11") (pinfunction "NC_11") (pintype "passive"))
    )
    (net (code "50") (name "unconnected-(U2B-NC-Pad12)") (class "Default")
      (node (ref "U2") (pin "12") (pinfunction "NC_12") (pintype "passive"))
    )
    (net (code "51") (name "unconnected-(U3-GRID5-Pad11)") (class "Default")
      (node (ref "U3") (pin "11") (pinfunction "GRID5_11") (pintype "output"))
    )
    (net (code "52") (name "unconnected-(U3-GRID6-Pad10)") (class "Default")
      (node (ref "U3") (pin "10") (pinfunction "GRID6_10") (pintype "output"))
    )
    (net (code "53") (name "unconnected-(U3-K1-Pad19)") (class "Default")
      (node (ref "U3") (pin "19") (pinfunction "K1_19") (pintype "input+no_connect"))
    )
    (net (code "54") (name "unconnected-(U3-K2-Pad20)") (class "Default")
      (node (ref "U3") (pin "20") (pinfunction "K2_20") (pintype "input+no_connect"))
    )
    (net (code "55") (name "unconnected-(U4-OSCIN_PA1-Pad5)") (class "Default")
      (node (ref "U4") (pin "5") (pinfunction "OSCIN_PA1_5") (pintype "bidirectional"))
    )
    (net (code "56") (name "unconnected-(U4-OSCOUT{slash}PA2-Pad6)") (class "Default")
      (node (ref "U4") (pin "6") (pinfunction "OSCOUT/PA2_6") (pintype "bidirectional"))
    )
    (net (code "57") (name "unconnected-(U4-PC4(HS){slash}TIM1_CH4{slash}CLK_CCO{slash}AIN2{slash}[TIM1_CH2N]-Pad14)") (class "Default")
      (node (ref "U4") (pin "14") (pinfunction "PC4(HS)/TIM1_CH4/CLK_CCO/AIN2/[TIM1_CH2N]_14") (pintype "bidirectional"))
    )
    (net (code "58") (name "unconnected-(U4-PC7(HS){slash}SPI_MISO[TIM1_CH2]-Pad17)") (class "Default")
      (node (ref "U4") (pin "17") (pinfunction "PC7(HS)/SPI_MISO[TIM1_CH2]_17") (pintype "bidirectional"))
    )
    (net (code "59") (name "unconnected-(U4-PD3(HS){slash}AIN4{slash}TIM2_CH2{slash}ADC_ETR-Pad20)") (class "Default")
      (node (ref "U4") (pin "20") (pinfunction "PD3(HS)/AIN4/TIM2_CH2/ADC_ETR_20") (pintype "bidirectional"))
    )
    (net (code "60") (name "unconnected-(U4-UART1_CK{slash}TIM2_CH1{slash}BEEP{slash}(HS)PD4-Pad1)") (class "Default")
      (node (ref "U4") (pin "1") (pinfunction "UART1_CK/TIM2_CH1/BEEP/(HS)PD4_1") (pintype "bidirectional"))
    )
  )
)
